# sao-iic.net
KiCad netlist of a schematic drawn in EAGLE
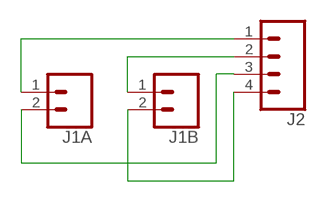
[diagram p0: schematic, sheet 1]

(export (version "E")
  (design (tool "Eeschema 10.0.6"))
  (components
    (comp (ref "J1A")
      (value "CONN_02LOCK")
      (footprint "eagle-import:1X02_LOCK")
      (libsource (lib "eagle-import") (part "CONN_02LOCK"))
    )
    (comp (ref "J1B")
      (value "CONN_02LOCK")
      (footprint "eagle-import:1X02_LOCK")
      (libsource (lib "eagle-import") (part "CONN_02LOCK"))
    )
    (comp (ref "J2")
      (value "CONN_04LOCK")
      (footprint "eagle-import:1X04_LOCK")
      (libsource (lib "eagle-import") (part "CONN_04LOCK"))
    )
  )
  (nets
    (net (code "1") (name "Net-(J1A-Pad1)") (class "Default")
      (node (ref "J1A") (pin "1") (pinfunction "1_1") (pintype "passive"))
      (node (ref "J2") (pin "1") (pinfunction "1_1") (pintype "passive"))
    )
    (net (code "2") (name "Net-(J1A-Pad2)") (class "Default")
      (node (ref "J1A") (pin "2") (pinfunction "2_2") (pintype "passive"))
      (node (ref "J2") (pin "3") (pinfunction "3_3") (pintype "passive"))
    )
    (net (code "3") (name "Net-(J1B-Pad1)") (class "Default")
      (node (ref "J1B") (pin "1") (pinfunction "1_1") (pintype "passive"))
      (node (ref "J2") (pin "2") (pinfunction "2_2") (pintype "passive"))
    )
    (net (code "4") (name "Net-(J1B-Pad2)") (class "Default")
      (node (ref "J1B") (pin "2") (pinfunction "2_2") (pintype "passive"))
      (node (ref "J2") (pin "4") (pinfunction "4_4") (pintype "passive"))
    )
  )
)
